# MCU.net
KiCad netlist of a schematic drawn in Altium Designer
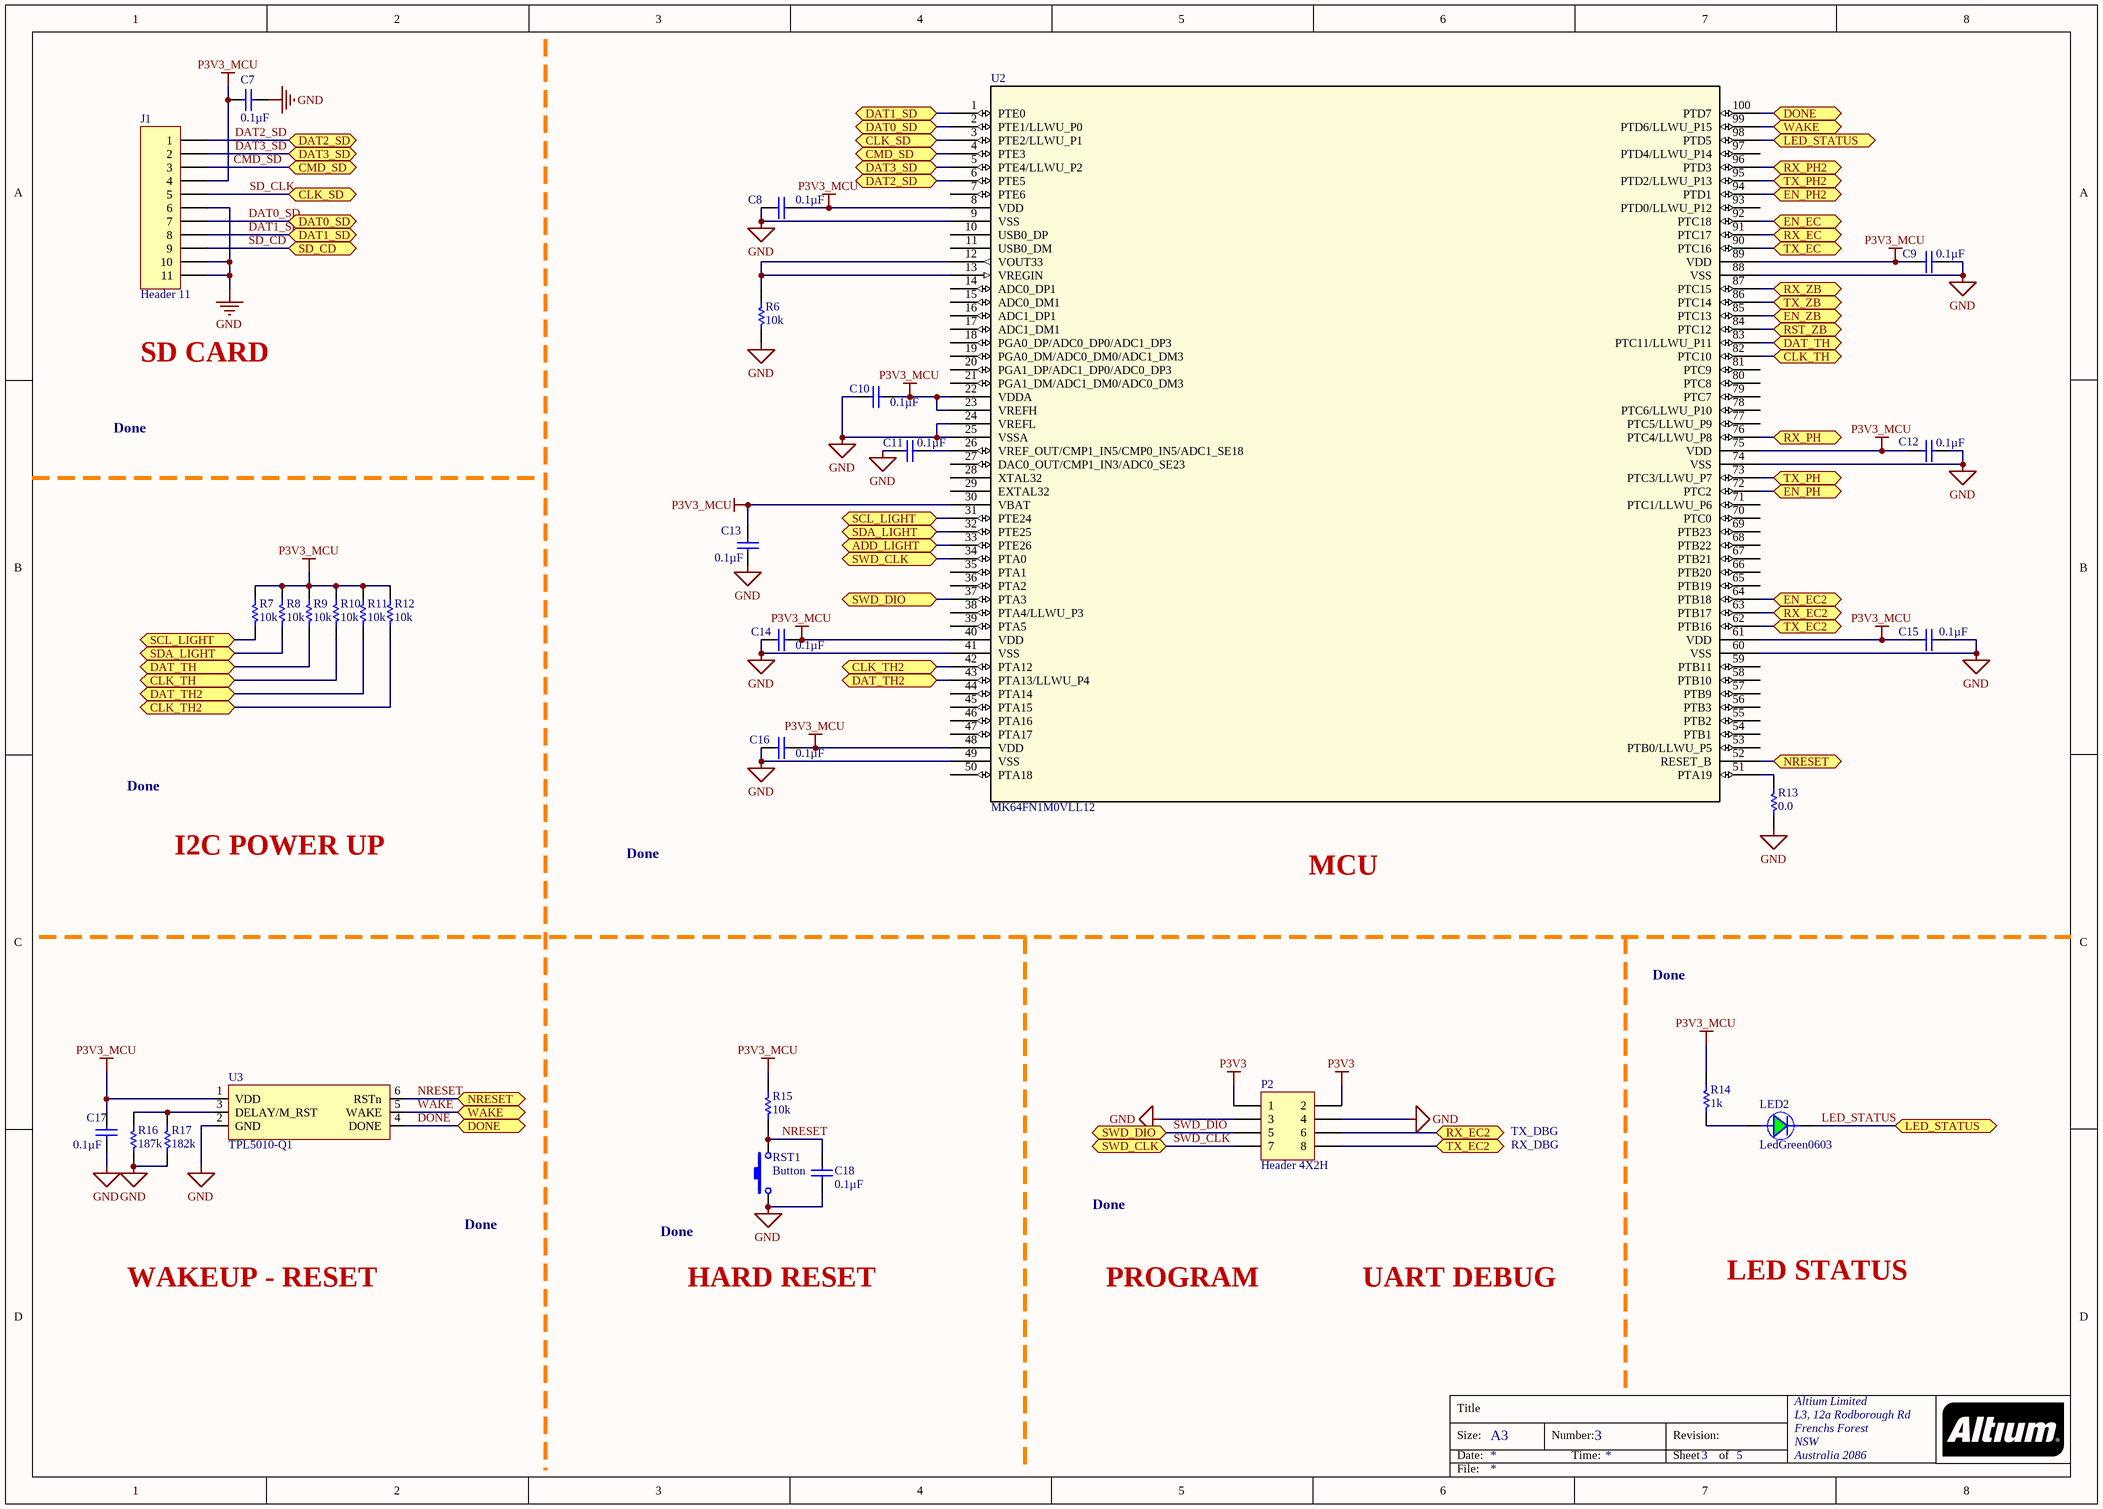
[diagram p0: MCU.SchDoc]

(export (version "E")
  (design (tool "Eeschema 10.0.6"))
  (components
    (comp (ref "C7")
      (value "0.1µF")
      (footprint "C0402M")
      (description "CAP CER 0.1UF 10V X7R 0402")
      (fields
        (field (name "MANUFACTURER") "Taiyo Yuden")
        (field (name "MANUFACTURER PART NUMBER") "LMK105B7104KVHF")
      )
      (libsource (lib "BinhLib") (part "CAP0.1u0402"))
    )
    (comp (ref "C8")
      (value "0.1µF")
      (footprint "C0402M")
      (description "CAP CER 0.1UF 10V X7R 0402")
      (fields
        (field (name "MANUFACTURER") "Taiyo Yuden")
        (field (name "MANUFACTURER PART NUMBER") "LMK105B7104KVHF")
      )
      (libsource (lib "BinhLib") (part "CAP0.1u0402"))
    )
    (comp (ref "C9")
      (value "0.1µF")
      (footprint "C0402M")
      (description "CAP CER 0.1UF 10V X7R 0402")
      (fields
        (field (name "MANUFACTURER") "Taiyo Yuden")
        (field (name "MANUFACTURER PART NUMBER") "LMK105B7104KVHF")
      )
      (libsource (lib "BinhLib") (part "CAP0.1u0402"))
    )
    (comp (ref "C10")
      (value "0.1µF")
      (footprint "C0402M")
      (description "CAP CER 0.1UF 10V X7R 0402")
      (fields
        (field (name "MANUFACTURER") "Taiyo Yuden")
        (field (name "MANUFACTURER PART NUMBER") "LMK105B7104KVHF")
      )
      (libsource (lib "BinhLib") (part "CAP0.1u0402"))
    )
    (comp (ref "C11")
      (value "0.1µF")
      (footprint "C0402M")
      (description "CAP CER 0.1UF 10V X7R 0402")
      (fields
        (field (name "MANUFACTURER") "Taiyo Yuden")
        (field (name "MANUFACTURER PART NUMBER") "LMK105B7104KVHF")
      )
      (libsource (lib "BinhLib") (part "CAP0.1u0402"))
    )
    (comp (ref "C12")
      (value "0.1µF")
      (footprint "C0402M")
      (description "CAP CER 0.1UF 10V X7R 0402")
      (fields
        (field (name "MANUFACTURER") "Taiyo Yuden")
        (field (name "MANUFACTURER PART NUMBER") "LMK105B7104KVHF")
      )
      (libsource (lib "BinhLib") (part "CAP0.1u0402"))
    )
    (comp (ref "C13")
      (value "0.1µF")
      (footprint "C0402M")
      (description "CAP CER 0.1UF 10V X7R 0402")
      (fields
        (field (name "MANUFACTURER") "Taiyo Yuden")
        (field (name "MANUFACTURER PART NUMBER") "LMK105B7104KVHF")
      )
      (libsource (lib "BinhLib") (part "CAP0.1u0402"))
    )
    (comp (ref "C14")
      (value "0.1µF")
      (footprint "C0402M")
      (description "CAP CER 0.1UF 10V X7R 0402")
      (fields
        (field (name "MANUFACTURER") "Taiyo Yuden")
        (field (name "MANUFACTURER PART NUMBER") "LMK105B7104KVHF")
      )
      (libsource (lib "BinhLib") (part "CAP0.1u0402"))
    )
    (comp (ref "C15")
      (value "0.1µF")
      (footprint "C0402M")
      (description "CAP CER 0.1UF 10V X7R 0402")
      (fields
        (field (name "MANUFACTURER") "Taiyo Yuden")
        (field (name "MANUFACTURER PART NUMBER") "LMK105B7104KVHF")
      )
      (libsource (lib "BinhLib") (part "CAP0.1u0402"))
    )
    (comp (ref "C16")
      (value "0.1µF")
      (footprint "C0402M")
      (description "CAP CER 0.1UF 10V X7R 0402")
      (fields
        (field (name "MANUFACTURER") "Taiyo Yuden")
        (field (name "MANUFACTURER PART NUMBER") "LMK105B7104KVHF")
      )
      (libsource (lib "BinhLib") (part "CAP0.1u0402"))
    )
    (comp (ref "C17")
      (value "0.1µF")
      (footprint "C0402M")
      (description "CAP CER 0.1UF 10V X7R 0402")
      (fields
        (field (name "MANUFACTURER") "Taiyo Yuden")
        (field (name "MANUFACTURER PART NUMBER") "LMK105B7104KVHF")
      )
      (libsource (lib "BinhLib") (part "CAP0.1u0402"))
    )
    (comp (ref "C18")
      (value "0.1µF")
      (footprint "C0402M")
      (description "CAP CER 0.1UF 10V X7R 0402")
      (fields
        (field (name "MANUFACTURER") "Taiyo Yuden")
        (field (name "MANUFACTURER PART NUMBER") "LMK105B7104KVHF")
      )
      (libsource (lib "BinhLib") (part "CAP0.1u0402"))
    )
    (comp (ref "J1")
      (value "Header 11")
      (footprint "TF_V3")
      (description "Header, 11-Pin")
      (fields (field (name "PUBLISHER") "Altium Limited"))
      (libsource (lib "Miscellaneous Connectors") (part "Header 11"))
    )
    (comp (ref "LED2")
      (value "LedGreen0603")
      (footprint "0603LED-GREEN")
      (description "LED GREEN CLEAR 0603 SMD")
      (fields
        (field (name "MANUFACTURER") "Everlight Electronics Co Ltd")
        (field (name "MANUFACTURER PART NUMBER") "QTLP601C4TR")
      )
      (libsource (lib "BinhLib") (part "LedGreen0603"))
    )
    (comp (ref "P2")
      (value "Header 4X2H")
      (footprint "HDR2X4")
      (description "Header, 4-Pin, Dual row, Right Angle")
      (fields (field (name "PUBLISHER") "Altium Limited"))
      (libsource (lib "BinhLib") (part "Header 4X2H"))
    )
    (comp (ref "R6")
      (value "10k")
      (footprint "R0603M")
      (description "RES SMD 10K OHM 1% 1/10W 0603")
      (fields
        (field (name "MANUFACTURER") "Panasonic Electronic Components")
        (field (name "MANUFACTURER PART NUMBER") "ERJ-3EKF1002V")
      )
      (libsource (lib "BinhLib") (part "RES10k0603"))
    )
    (comp (ref "R7")
      (value "10k")
      (footprint "R0603M")
      (description "RES SMD 10K OHM 1% 1/10W 0603")
      (fields
        (field (name "MANUFACTURER") "Panasonic Electronic Components")
        (field (name "MANUFACTURER PART NUMBER") "ERJ-3EKF1002V")
      )
      (libsource (lib "BinhLib") (part "RES10k0603"))
    )
    (comp (ref "R8")
      (value "10k")
      (footprint "R0603M")
      (description "RES SMD 10K OHM 1% 1/10W 0603")
      (fields
        (field (name "MANUFACTURER") "Panasonic Electronic Components")
        (field (name "MANUFACTURER PART NUMBER") "ERJ-3EKF1002V")
      )
      (libsource (lib "BinhLib") (part "RES10k0603"))
    )
    (comp (ref "R9")
      (value "10k")
      (footprint "R0603M")
      (description "RES SMD 10K OHM 1% 1/10W 0603")
      (fields
        (field (name "MANUFACTURER") "Panasonic Electronic Components")
        (field (name "MANUFACTURER PART NUMBER") "ERJ-3EKF1002V")
      )
      (libsource (lib "BinhLib") (part "RES10k0603"))
    )
    (comp (ref "R10")
      (value "10k")
      (footprint "R0603M")
      (description "RES SMD 10K OHM 1% 1/10W 0603")
      (fields
        (field (name "MANUFACTURER") "Panasonic Electronic Components")
        (field (name "MANUFACTURER PART NUMBER") "ERJ-3EKF1002V")
      )
      (libsource (lib "BinhLib") (part "RES10k0603"))
    )
    (comp (ref "R11")
      (value "10k")
      (footprint "R0603M")
      (description "RES SMD 10K OHM 1% 1/10W 0603")
      (fields
        (field (name "MANUFACTURER") "Panasonic Electronic Components")
        (field (name "MANUFACTURER PART NUMBER") "ERJ-3EKF1002V")
      )
      (libsource (lib "BinhLib") (part "RES10k0603"))
    )
    (comp (ref "R12")
      (value "10k")
      (footprint "R0603M")
      (description "RES SMD 10K OHM 1% 1/10W 0603")
      (fields
        (field (name "MANUFACTURER") "Panasonic Electronic Components")
        (field (name "MANUFACTURER PART NUMBER") "ERJ-3EKF1002V")
      )
      (libsource (lib "BinhLib") (part "RES10k0603"))
    )
    (comp (ref "R13")
      (value "0.0")
      (footprint "R0603M")
      (description "RES SMD 0.0OHM JUMPER 1/10W 0603")
      (fields
        (field (name "MANUFACTURER") "Panasonic Electronic Components")
        (field (name "MANUFACTURER PART NUMBER") "ERJ-3GEY0R00V")
      )
      (libsource (lib "BinhLib") (part "RES00603"))
    )
    (comp (ref "R14")
      (value "1k")
      (footprint "R0603M")
      (description "RES SMD 1K OHM 1% 1/10W 0603")
      (fields
        (field (name "MANUFACTURER") "Panasonic Electronic Components")
        (field (name "MANUFACTURER PART NUMBER") "ERJ-3EKF1001V")
      )
      (libsource (lib "BinhLib") (part "RES1k0603"))
    )
    (comp (ref "R15")
      (value "10k")
      (footprint "R0603M")
      (description "RES SMD 10K OHM 1% 1/10W 0603")
      (fields
        (field (name "MANUFACTURER") "Panasonic Electronic Components")
        (field (name "MANUFACTURER PART NUMBER") "ERJ-3EKF1002V")
      )
      (libsource (lib "BinhLib") (part "RES10k0603"))
    )
    (comp (ref "R16")
      (value "187k")
      (footprint "R0603M")
      (description "RES SMD 187K OHM 1% 1/10W 0603")
      (fields
        (field (name "MANUFACTURER") "Panasonic Electronic Components")
        (field (name "MANUFACTURER PART NUMBER") "ERJ-3EKF1873V")
      )
      (libsource (lib "BinhLib") (part "Resistor"))
    )
    (comp (ref "R17")
      (value "182k")
      (footprint "R0603M")
      (description "RES SMD 182K OHM 1% 1/10W 0603")
      (fields
        (field (name "MANUFACTURER") "Panasonic Electronic Components")
        (field (name "MANUFACTURER PART NUMBER") "ERJ-3EKF1823V")
      )
      (libsource (lib "BinhLib") (part "Resistor"))
    )
    (comp (ref "RST1") (value "Button") (footprint "SWSMD") (libsource (lib "BinhLib") (part "Button")))
    (comp (ref "U2")
      (value "MK64FN1M0VLL12")
      (footprint "LQFP-100_14X14X1")
      (description "IC MCU 32BIT 1MB FLASH 100LQFP")
      (fields (field (name "MANUFACTURER") "NXP USA Inc."))
      (libsource (lib "BinhLib") (part "MK64FN1M0VLL12"))
    )
    (comp (ref "U3")
      (value "TPL5010-Q1")
      (footprint "SOT23-6")
      (description "IC TIMER W/WATCHDOG 6SOT")
      (fields
        (field (name "MANUFACTURER") "Texas Instruments")
        (field (name "MANUFACTURER PART NUMBER") "TPL5010QDDCRQ1")
      )
      (libsource (lib "BinhLib") (part "TPL5010"))
    )
  )
  (nets
    (net (code "1") (name "/ADD_LIGHT") (class "Default")
      (node (ref "U2") (pin "33") (pinfunction "PTE26_33") (pintype "bidirectional"))
    )
    (net (code "2") (name "/CLK_TH") (class "Default")
      (node (ref "R10") (pin "1") (pinfunction "1_1") (pintype "passive"))
      (node (ref "U2") (pin "82") (pinfunction "PTC10_82") (pintype "bidirectional"))
    )
    (net (code "3") (name "/CLK_TH2") (class "Default")
      (node (ref "R12") (pin "1") (pinfunction "1_1") (pintype "passive"))
      (node (ref "U2") (pin "42") (pinfunction "PTA12_42") (pintype "bidirectional"))
    )
    (net (code "4") (name "/CMD_SD") (class "Default")
      (node (ref "J1") (pin "3") (pinfunction "3_3") (pintype "passive"))
      (node (ref "U2") (pin "4") (pinfunction "PTE3_4") (pintype "bidirectional"))
    )
    (net (code "5") (name "/DAT0_SD") (class "Default")
      (node (ref "J1") (pin "7") (pinfunction "7_7") (pintype "passive"))
      (node (ref "U2") (pin "2") (pinfunction "PTE1/LLWU_P0_2") (pintype "bidirectional"))
    )
    (net (code "6") (name "/DAT1_SD") (class "Default")
      (node (ref "J1") (pin "8") (pinfunction "8_8") (pintype "passive"))
      (node (ref "U2") (pin "1") (pinfunction "PTE0_1") (pintype "bidirectional"))
    )
    (net (code "7") (name "/DAT2_SD") (class "Default")
      (node (ref "J1") (pin "1") (pinfunction "1_1") (pintype "passive"))
      (node (ref "U2") (pin "6") (pinfunction "PTE5_6") (pintype "bidirectional"))
    )
    (net (code "8") (name "/DAT3_SD") (class "Default")
      (node (ref "J1") (pin "2") (pinfunction "2_2") (pintype "passive"))
      (node (ref "U2") (pin "5") (pinfunction "PTE4/LLWU_P2_5") (pintype "bidirectional"))
    )
    (net (code "9") (name "/DAT_TH") (class "Default")
      (node (ref "R9") (pin "1") (pinfunction "1_1") (pintype "passive"))
      (node (ref "U2") (pin "83") (pinfunction "PTC11/LLWU_P11_83") (pintype "bidirectional"))
    )
    (net (code "10") (name "/DAT_TH2") (class "Default")
      (node (ref "R11") (pin "1") (pinfunction "1_1") (pintype "passive"))
      (node (ref "U2") (pin "43") (pinfunction "PTA13/LLWU_P4_43") (pintype "bidirectional"))
    )
    (net (code "11") (name "/DONE") (class "Default")
      (node (ref "U2") (pin "100") (pinfunction "PTD7_100") (pintype "bidirectional"))
      (node (ref "U3") (pin "4") (pinfunction "DONE_4") (pintype "passive"))
    )
    (net (code "12") (name "/EN_EC") (class "Default")
      (node (ref "U2") (pin "92") (pinfunction "PTC18_92") (pintype "bidirectional"))
    )
    (net (code "13") (name "/EN_EC2") (class "Default")
      (node (ref "U2") (pin "64") (pinfunction "PTB18_64") (pintype "bidirectional"))
    )
    (net (code "14") (name "/EN_PH") (class "Default")
      (node (ref "U2") (pin "72") (pinfunction "PTC2_72") (pintype "bidirectional"))
    )
    (net (code "15") (name "/EN_PH2") (class "Default")
      (node (ref "U2") (pin "94") (pinfunction "PTD1_94") (pintype "bidirectional"))
    )
    (net (code "16") (name "/EN_ZB") (class "Default")
      (node (ref "U2") (pin "85") (pinfunction "PTC13_85") (pintype "bidirectional"))
    )
    (net (code "17") (name "/LED_STATUS") (class "Default")
      (node (ref "LED2") (pin "2") (pinfunction "Katot_2") (pintype "passive"))
      (node (ref "U2") (pin "98") (pinfunction "PTD5_98") (pintype "bidirectional"))
    )
    (net (code "18") (name "/NRESET") (class "Default")
      (node (ref "C18") (pin "2") (pintype "passive"))
      (node (ref "R15") (pin "2") (pinfunction "2_2") (pintype "passive"))
      (node (ref "RST1") (pin "2") (pinfunction "2_2") (pintype "passive"))
      (node (ref "U2") (pin "52") (pinfunction "RESET_B_52") (pintype "passive"))
      (node (ref "U3") (pin "6") (pinfunction "RSTn_6") (pintype "passive"))
    )
    (net (code "19") (name "/RST_ZB") (class "Default")
      (node (ref "U2") (pin "84") (pinfunction "PTC12_84") (pintype "bidirectional"))
    )
    (net (code "20") (name "/RX_EC") (class "Default")
      (node (ref "U2") (pin "91") (pinfunction "PTC17_91") (pintype "bidirectional"))
    )
    (net (code "21") (name "/RX_EC2") (class "Default")
      (node (ref "P2") (pin "6") (pinfunction "6_6") (pintype "passive"))
      (node (ref "U2") (pin "63") (pinfunction "PTB17_63") (pintype "bidirectional"))
    )
    (net (code "22") (name "/RX_PH") (class "Default")
      (node (ref "U2") (pin "76") (pinfunction "PTC4/LLWU_P8_76") (pintype "bidirectional"))
    )
    (net (code "23") (name "/RX_PH2") (class "Default")
      (node (ref "U2") (pin "96") (pinfunction "PTD3_96") (pintype "bidirectional"))
    )
    (net (code "24") (name "/RX_ZB") (class "Default")
      (node (ref "U2") (pin "87") (pinfunction "PTC15_87") (pintype "bidirectional"))
    )
    (net (code "25") (name "/SCL_LIGHT") (class "Default")
      (node (ref "R7") (pin "1") (pinfunction "1_1") (pintype "passive"))
      (node (ref "U2") (pin "31") (pinfunction "PTE24_31") (pintype "bidirectional"))
    )
    (net (code "26") (name "/SDA_LIGHT") (class "Default")
      (node (ref "R8") (pin "1") (pinfunction "1_1") (pintype "passive"))
      (node (ref "U2") (pin "32") (pinfunction "PTE25_32") (pintype "bidirectional"))
    )
    (net (code "27") (name "/SD_CD") (class "Default")
      (node (ref "J1") (pin "9") (pinfunction "9_9") (pintype "passive"))
    )
    (net (code "28") (name "/SD_CLK") (class "Default")
      (node (ref "J1") (pin "5") (pinfunction "5_5") (pintype "passive"))
      (node (ref "U2") (pin "3") (pinfunction "PTE2/LLWU_P1_3") (pintype "bidirectional"))
    )
    (net (code "29") (name "/SWD_CLK") (class "Default")
      (node (ref "P2") (pin "7") (pinfunction "7_7") (pintype "passive"))
      (node (ref "U2") (pin "34") (pinfunction "PTA0_34") (pintype "bidirectional"))
    )
    (net (code "30") (name "/SWD_DIO") (class "Default")
      (node (ref "P2") (pin "5") (pinfunction "5_5") (pintype "passive"))
      (node (ref "U2") (pin "37") (pinfunction "PTA3_37") (pintype "bidirectional"))
    )
    (net (code "31") (name "/TX_EC") (class "Default")
      (node (ref "U2") (pin "90") (pinfunction "PTC16_90") (pintype "bidirectional"))
    )
    (net (code "32") (name "/TX_EC2") (class "Default")
      (node (ref "P2") (pin "8") (pinfunction "8_8") (pintype "passive"))
      (node (ref "U2") (pin "62") (pinfunction "PTB16_62") (pintype "bidirectional"))
    )
    (net (code "33") (name "/TX_PH") (class "Default")
      (node (ref "U2") (pin "73") (pinfunction "PTC3/LLWU_P7_73") (pintype "bidirectional"))
    )
    (net (code "34") (name "/TX_PH2") (class "Default")
      (node (ref "U2") (pin "95") (pinfunction "PTD2/LLWU_P13_95") (pintype "bidirectional"))
    )
    (net (code "35") (name "/TX_ZB") (class "Default")
      (node (ref "U2") (pin "86") (pinfunction "PTC14_86") (pintype "bidirectional"))
    )
    (net (code "36") (name "/WAKE") (class "Default")
      (node (ref "U2") (pin "99") (pinfunction "PTD6/LLWU_P15_99") (pintype "bidirectional"))
      (node (ref "U3") (pin "5") (pinfunction "WAKE_5") (pintype "passive"))
    )
    (net (code "37") (name "GND") (class "Default")
      (node (ref "C10") (pin "2") (pintype "passive"))
      (node (ref "C11") (pin "2") (pintype "passive"))
      (node (ref "C12") (pin "2") (pintype "passive"))
      (node (ref "C13") (pin "2") (pintype "passive"))
      (node (ref "C14") (pin "1") (pintype "passive"))
      (node (ref "C15") (pin "2") (pintype "passive"))
      (node (ref "C16") (pin "1") (pintype "passive"))
      (node (ref "C17") (pin "1") (pintype "passive"))
      (node (ref "C18") (pin "1") (pintype "passive"))
      (node (ref "C7") (pin "2") (pintype "passive"))
      (node (ref "C8") (pin "2") (pintype "passive"))
      (node (ref "C9") (pin "2") (pintype "passive"))
      (node (ref "J1") (pin "10") (pinfunction "10_10") (pintype "passive"))
      (node (ref "J1") (pin "11") (pinfunction "11_11") (pintype "passive"))
      (node (ref "J1") (pin "6") (pinfunction "6_6") (pintype "passive"))
      (node (ref "P2") (pin "3") (pinfunction "3_3") (pintype "passive"))
      (node (ref "P2") (pin "4") (pinfunction "4_4") (pintype "passive"))
      (node (ref "R13") (pin "1") (pinfunction "1_1") (pintype "passive"))
      (node (ref "R16") (pin "1") (pinfunction "1_1") (pintype "passive"))
      (node (ref "R17") (pin "1") (pinfunction "1_1") (pintype "passive"))
      (node (ref "R6") (pin "1") (pinfunction "1_1") (pintype "passive"))
      (node (ref "RST1") (pin "1") (pinfunction "1_1") (pintype "passive"))
      (node (ref "U2") (pin "24") (pinfunction "VREFL_24") (pintype "power_in"))
      (node (ref "U2") (pin "25") (pinfunction "VSSA_25") (pintype "power_in"))
      (node (ref "U2") (pin "41") (pinfunction "VSS_41") (pintype "power_in"))
      (node (ref "U2") (pin "49") (pinfunction "VSS_49") (pintype "power_in"))
      (node (ref "U2") (pin "60") (pinfunction "VSS_60") (pintype "power_in"))
      (node (ref "U2") (pin "74") (pinfunction "VSS_74") (pintype "power_in"))
      (node (ref "U2") (pin "88") (pinfunction "VSS_88") (pintype "power_in"))
      (node (ref "U2") (pin "9") (pinfunction "VSS_9") (pintype "power_in"))
      (node (ref "U3") (pin "2") (pinfunction "GND_2") (pintype "passive"))
    )
    (net (code "38") (name "Net-(LED2-anot)") (class "Default")
      (node (ref "LED2") (pin "1") (pinfunction "anot_1") (pintype "passive"))
      (node (ref "R14") (pin "2") (pinfunction "2_2") (pintype "passive"))
    )
    (net (code "39") (name "Net-(U2-PTA19)") (class "Default")
      (node (ref "R13") (pin "2") (pinfunction "2_2") (pintype "passive"))
      (node (ref "U2") (pin "51") (pinfunction "PTA19_51") (pintype "bidirectional"))
    )
    (net (code "40") (name "Net-(U2-VOUT33)") (class "Default")
      (node (ref "R6") (pin "2") (pinfunction "2_2") (pintype "passive"))
      (node (ref "U2") (pin "12") (pinfunction "VOUT33_12") (pintype "output"))
      (node (ref "U2") (pin "13") (pinfunction "VREGIN_13") (pintype "input"))
    )
    (net (code "41") (name "Net-(U2-VREF_OUT{slash}CMP1_IN5{slash}CMP0_IN5{slash}ADC1_SE18)") (class "Default")
      (node (ref "C11") (pin "1") (pintype "passive"))
      (node (ref "U2") (pin "26") (pinfunction "VREF_OUT/CMP1_IN5/CMP0_IN5/ADC1_SE18_26") (pintype "bidirectional"))
    )
    (net (code "42") (name "Net-(U3-DELAY{slash}M_RST)") (class "Default")
      (node (ref "R16") (pin "2") (pinfunction "2_2") (pintype "passive"))
      (node (ref "R17") (pin "2") (pinfunction "2_2") (pintype "passive"))
      (node (ref "U3") (pin "3") (pinfunction "DELAY/M_RST_3") (pintype "passive"))
    )
    (net (code "43") (name "P3V3") (class "Default")
      (node (ref "P2") (pin "1") (pinfunction "1_1") (pintype "passive"))
      (node (ref "P2") (pin "2") (pinfunction "2_2") (pintype "passive"))
    )
    (net (code "44") (name "P3V3_MCU") (class "Default")
      (node (ref "C10") (pin "1") (pintype "passive"))
      (node (ref "C12") (pin "1") (pintype "passive"))
      (node (ref "C13") (pin "1") (pintype "passive"))
      (node (ref "C14") (pin "2") (pintype "passive"))
      (node (ref "C15") (pin "1") (pintype "passive"))
      (node (ref "C16") (pin "2") (pintype "passive"))
      (node (ref "C17") (pin "2") (pintype "passive"))
      (node (ref "C7") (pin "1") (pintype "passive"))
      (node (ref "C8") (pin "1") (pintype "passive"))
      (node (ref "C9") (pin "1") (pintype "passive"))
      (node (ref "J1") (pin "4") (pinfunction "4_4") (pintype "passive"))
      (node (ref "R10") (pin "2") (pinfunction "2_2") (pintype "passive"))
      (node (ref "R11") (pin "2") (pinfunction "2_2") (pintype "passive"))
      (node (ref "R12") (pin "2") (pinfunction "2_2") (pintype "passive"))
      (node (ref "R14") (pin "1") (pinfunction "1_1") (pintype "passive"))
      (node (ref "R15") (pin "1") (pinfunction "1_1") (pintype "passive"))
      (node (ref "R7") (pin "2") (pinfunction "2_2") (pintype "passive"))
      (node (ref "R8") (pin "2") (pinfunction "2_2") (pintype "passive"))
      (node (ref "R9") (pin "2") (pinfunction "2_2") (pintype "passive"))
      (node (ref "U2") (pin "22") (pinfunction "VDDA_22") (pintype "power_in"))
      (node (ref "U2") (pin "23") (pinfunction "VREFH_23") (pintype "power_in"))
      (node (ref "U2") (pin "30") (pinfunction "VBAT_30") (pintype "power_in"))
      (node (ref "U2") (pin "40") (pinfunction "VDD_40") (pintype "power_in"))
      (node (ref "U2") (pin "48") (pinfunction "VDD_48") (pintype "power_in"))
      (node (ref "U2") (pin "61") (pinfunction "VDD_61") (pintype "power_in"))
      (node (ref "U2") (pin "75") (pinfunction "VDD_75") (pintype "power_in"))
      (node (ref "U2") (pin "8") (pinfunction "VDD_8") (pintype "power_in"))
      (node (ref "U2") (pin "89") (pinfunction "VDD_89") (pintype "power_in"))
      (node (ref "U3") (pin "1") (pinfunction "VDD_1") (pintype "passive"))
    )
    (net (code "45") (name "unconnected-(U2-ADC0_DM1-Pad15)") (class "Default")
      (node (ref "U2") (pin "15") (pinfunction "ADC0_DM1_15") (pintype "bidirectional"))
    )
    (net (code "46") (name "unconnected-(U2-ADC0_DP1-Pad14)") (class "Default")
      (node (ref "U2") (pin "14") (pinfunction "ADC0_DP1_14") (pintype "bidirectional"))
    )
    (net (code "47") (name "unconnected-(U2-ADC1_DM1-Pad17)") (class "Default")
      (node (ref "U2") (pin "17") (pinfunction "ADC1_DM1_17") (pintype "bidirectional"))
    )
    (net (code "48") (name "unconnected-(U2-ADC1_DP1-Pad16)") (class "Default")
      (node (ref "U2") (pin "16") (pinfunction "ADC1_DP1_16") (pintype "bidirectional"))
    )
    (net (code "49") (name "unconnected-(U2-DAC0_OUT{slash}CMP1_IN3{slash}ADC0_SE23-Pad27)") (class "Default")
      (node (ref "U2") (pin "27") (pinfunction "DAC0_OUT/CMP1_IN3/ADC0_SE23_27") (pintype "bidirectional"))
    )
    (net (code "50") (name "unconnected-(U2-EXTAL32-Pad29)") (class "Default")
      (node (ref "U2") (pin "29") (pinfunction "EXTAL32_29") (pintype "passive"))
    )
    (net (code "51") (name "unconnected-(U2-PGA0_DM{slash}ADC0_DM0{slash}ADC1_DM3-Pad19)") (class "Default")
      (node (ref "U2") (pin "19") (pinfunction "PGA0_DM/ADC0_DM0/ADC1_DM3_19") (pintype "bidirectional"))
    )
    (net (code "52") (name "unconnected-(U2-PGA0_DP{slash}ADC0_DP0{slash}ADC1_DP3-Pad18)") (class "Default")
      (node (ref "U2") (pin "18") (pinfunction "PGA0_DP/ADC0_DP0/ADC1_DP3_18") (pintype "bidirectional"))
    )
    (net (code "53") (name "unconnected-(U2-PGA1_DM{slash}ADC1_DM0{slash}ADC0_DM3-Pad21)") (class "Default")
      (node (ref "U2") (pin "21") (pinfunction "PGA1_DM/ADC1_DM0/ADC0_DM3_21") (pintype "bidirectional"))
    )
    (net (code "54") (name "unconnected-(U2-PGA1_DP{slash}ADC1_DP0{slash}ADC0_DP3-Pad20)") (class "Default")
      (node (ref "U2") (pin "20") (pinfunction "PGA1_DP/ADC1_DP0/ADC0_DP3_20") (pintype "bidirectional"))
    )
    (net (code "55") (name "unconnected-(U2-PTA1-Pad35)") (class "Default")
      (node (ref "U2") (pin "35") (pinfunction "PTA1_35") (pintype "bidirectional"))
    )
    (net (code "56") (name "unconnected-(U2-PTA2-Pad36)") (class "Default")
      (node (ref "U2") (pin "36") (pinfunction "PTA2_36") (pintype "bidirectional"))
    )
    (net (code "57") (name "unconnected-(U2-PTA4{slash}LLWU_P3-Pad38)") (class "Default")
      (node (ref "U2") (pin "38") (pinfunction "PTA4/LLWU_P3_38") (pintype "bidirectional"))
    )
    (net (code "58") (name "unconnected-(U2-PTA5-Pad39)") (class "Default")
      (node (ref "U2") (pin "39") (pinfunction "PTA5_39") (pintype "bidirectional"))
    )
    (net (code "59") (name "unconnected-(U2-PTA14-Pad44)") (class "Default")
      (node (ref "U2") (pin "44") (pinfunction "PTA14_44") (pintype "bidirectional"))
    )
    (net (code "60") (name "unconnected-(U2-PTA15-Pad45)") (class "Default")
      (node (ref "U2") (pin "45") (pinfunction "PTA15_45") (pintype "bidirectional"))
    )
    (net (code "61") (name "unconnected-(U2-PTA16-Pad46)") (class "Default")
      (node (ref "U2") (pin "46") (pinfunction "PTA16_46") (pintype "bidirectional"))
    )
    (net (code "62") (name "unconnected-(U2-PTA17-Pad47)") (class "Default")
      (node (ref "U2") (pin "47") (pinfunction "PTA17_47") (pintype "bidirectional"))
    )
    (net (code "63") (name "unconnected-(U2-PTA18-Pad50)") (class "Default")
      (node (ref "U2") (pin "50") (pinfunction "PTA18_50") (pintype "bidirectional"))
    )
    (net (code "64") (name "unconnected-(U2-PTB0{slash}LLWU_P5-Pad53)") (class "Default")
      (node (ref "U2") (pin "53") (pinfunction "PTB0/LLWU_P5_53") (pintype "bidirectional"))
    )
    (net (code "65") (name "unconnected-(U2-PTB1-Pad54)") (class "Default")
      (node (ref "U2") (pin "54") (pinfunction "PTB1_54") (pintype "bidirectional"))
    )
    (net (code "66") (name "unconnected-(U2-PTB2-Pad55)") (class "Default")
      (node (ref "U2") (pin "55") (pinfunction "PTB2_55") (pintype "bidirectional"))
    )
    (net (code "67") (name "unconnected-(U2-PTB3-Pad56)") (class "Default")
      (node (ref "U2") (pin "56") (pinfunction "PTB3_56") (pintype "bidirectional"))
    )
    (net (code "68") (name "unconnected-(U2-PTB9-Pad57)") (class "Default")
      (node (ref "U2") (pin "57") (pinfunction "PTB9_57") (pintype "bidirectional"))
    )
    (net (code "69") (name "unconnected-(U2-PTB10-Pad58)") (class "Default")
      (node (ref "U2") (pin "58") (pinfunction "PTB10_58") (pintype "bidirectional"))
    )
    (net (code "70") (name "unconnected-(U2-PTB11-Pad59)") (class "Default")
      (node (ref "U2") (pin "59") (pinfunction "PTB11_59") (pintype "bidirectional"))
    )
    (net (code "71") (name "unconnected-(U2-PTB19-Pad65)") (class "Default")
      (node (ref "U2") (pin "65") (pinfunction "PTB19_65") (pintype "bidirectional"))
    )
    (net (code "72") (name "unconnected-(U2-PTB20-Pad66)") (class "Default")
      (node (ref "U2") (pin "66") (pinfunction "PTB20_66") (pintype "bidirectional"))
    )
    (net (code "73") (name "unconnected-(U2-PTB21-Pad67)") (class "Default")
      (node (ref "U2") (pin "67") (pinfunction "PTB21_67") (pintype "bidirectional"))
    )
    (net (code "74") (name "unconnected-(U2-PTB22-Pad68)") (class "Default")
      (node (ref "U2") (pin "68") (pinfunction "PTB22_68") (pintype "bidirectional"))
    )
    (net (code "75") (name "unconnected-(U2-PTB23-Pad69)") (class "Default")
      (node (ref "U2") (pin "69") (pinfunction "PTB23_69") (pintype "bidirectional"))
    )
    (net (code "76") (name "unconnected-(U2-PTC0-Pad70)") (class "Default")
      (node (ref "U2") (pin "70") (pinfunction "PTC0_70") (pintype "bidirectional"))
    )
    (net (code "77") (name "unconnected-(U2-PTC1{slash}LLWU_P6-Pad71)") (class "Default")
      (node (ref "U2") (pin "71") (pinfunction "PTC1/LLWU_P6_71") (pintype "bidirectional"))
    )
    (net (code "78") (name "unconnected-(U2-PTC5{slash}LLWU_P9-Pad77)") (class "Default")
      (node (ref "U2") (pin "77") (pinfunction "PTC5/LLWU_P9_77") (pintype "bidirectional"))
    )
    (net (code "79") (name "unconnected-(U2-PTC6{slash}LLWU_P10-Pad78)") (class "Default")
      (node (ref "U2") (pin "78") (pinfunction "PTC6/LLWU_P10_78") (pintype "bidirectional"))
    )
    (net (code "80") (name "unconnected-(U2-PTC7-Pad79)") (class "Default")
      (node (ref "U2") (pin "79") (pinfunction "PTC7_79") (pintype "bidirectional"))
    )
    (net (code "81") (name "unconnected-(U2-PTC8-Pad80)") (class "Default")
      (node (ref "U2") (pin "80") (pinfunction "PTC8_80") (pintype "bidirectional"))
    )
    (net (code "82") (name "unconnected-(U2-PTC9-Pad81)") (class "Default")
      (node (ref "U2") (pin "81") (pinfunction "PTC9_81") (pintype "bidirectional"))
    )
    (net (code "83") (name "unconnected-(U2-PTD0{slash}LLWU_P12-Pad93)") (class "Default")
      (node (ref "U2") (pin "93") (pinfunction "PTD0/LLWU_P12_93") (pintype "bidirectional"))
    )
    (net (code "84") (name "unconnected-(U2-PTD4{slash}LLWU_P14-Pad97)") (class "Default")
      (node (ref "U2") (pin "97") (pinfunction "PTD4/LLWU_P14_97") (pintype "bidirectional"))
    )
    (net (code "85") (name "unconnected-(U2-PTE6-Pad7)") (class "Default")
      (node (ref "U2") (pin "7") (pinfunction "PTE6_7") (pintype "bidirectional"))
    )
    (net (code "86") (name "unconnected-(U2-USB0_DM-Pad11)") (class "Default")
      (node (ref "U2") (pin "11") (pinfunction "USB0_DM_11") (pintype "passive"))
    )
    (net (code "87") (name "unconnected-(U2-USB0_DP-Pad10)") (class "Default")
      (node (ref "U2") (pin "10") (pinfunction "USB0_DP_10") (pintype "passive"))
    )
    (net (code "88") (name "unconnected-(U2-XTAL32-Pad28)") (class "Default")
      (node (ref "U2") (pin "28") (pinfunction "XTAL32_28") (pintype "passive"))
    )
  )
)
